# RADIO.net
KiCad netlist of a schematic drawn in EAGLE
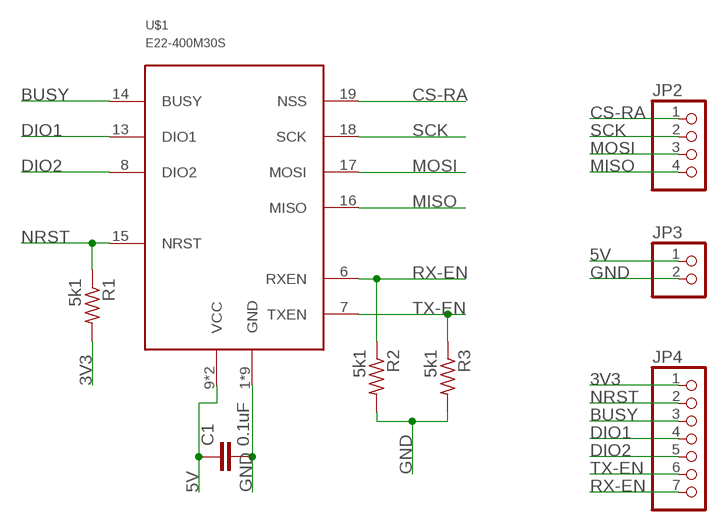
[diagram p0: schematic, sheet 1]

(export (version "E")
  (design (tool "Eeschema 10.0.6"))
  (components
    (comp (ref "C1")
      (value "0.1uF")
      (footprint "eagle-import:C0603")
      (libsource (lib "eagle-import") (part "C-EUC0603"))
    )
    (comp (ref "JP2")
      (value "PINHD-1X4")
      (footprint "eagle-import:1X04")
      (libsource (lib "eagle-import") (part "PINHD-1X4"))
    )
    (comp (ref "JP3")
      (value "PINHD-1X2")
      (footprint "eagle-import:1X02")
      (libsource (lib "eagle-import") (part "PINHD-1X2"))
    )
    (comp (ref "JP4")
      (value "PINHD-1X7")
      (footprint "eagle-import:1X07")
      (libsource (lib "eagle-import") (part "PINHD-1X7"))
    )
    (comp (ref "R1")
      (value "5k1")
      (footprint "eagle-import:R0603")
      (libsource (lib "eagle-import") (part "R-US_R0603"))
    )
    (comp (ref "R2")
      (value "5k1")
      (footprint "eagle-import:R0603")
      (libsource (lib "eagle-import") (part "R-US_R0603"))
    )
    (comp (ref "R3")
      (value "5k1")
      (footprint "eagle-import:R0603")
      (libsource (lib "eagle-import") (part "R-US_R0603"))
    )
    (comp (ref "U$1")
      (value "E22-400M30S")
      (footprint "eagle-import:E22-400M30S")
      (libsource (lib "eagle-import") (part "E22-400M30S"))
    )
  )
  (nets
    (net (code "1") (name "/3V3") (class "Default")
      (node (ref "JP4") (pin "1") (pinfunction "1_1") (pintype "passive"))
      (node (ref "R1") (pin "2") (pinfunction "2_2") (pintype "passive"))
    )
    (net (code "2") (name "/5V") (class "Default")
      (node (ref "C1") (pin "1") (pinfunction "1_1") (pintype "passive"))
      (node (ref "JP3") (pin "1") (pinfunction "1_1") (pintype "passive"))
      (node (ref "U$1") (pin "10") (pinfunction "VCC_10") (pintype "power_in"))
      (node (ref "U$1") (pin "9") (pinfunction "VCC_9") (pintype "power_in"))
    )
    (net (code "3") (name "/BUSY") (class "Default")
      (node (ref "JP4") (pin "3") (pinfunction "3_3") (pintype "passive"))
      (node (ref "U$1") (pin "14") (pinfunction "BUSY_14") (pintype "output"))
    )
    (net (code "4") (name "/CS-RA") (class "Default")
      (node (ref "JP2") (pin "1") (pinfunction "1_1") (pintype "passive"))
      (node (ref "U$1") (pin "19") (pinfunction "NSS_19") (pintype "input"))
    )
    (net (code "5") (name "/DIO1") (class "Default")
      (node (ref "JP4") (pin "4") (pinfunction "4_4") (pintype "passive"))
      (node (ref "U$1") (pin "13") (pinfunction "DIO1_13") (pintype "bidirectional"))
    )
    (net (code "6") (name "/DIO2") (class "Default")
      (node (ref "JP4") (pin "5") (pinfunction "5_5") (pintype "passive"))
      (node (ref "U$1") (pin "8") (pinfunction "DIO2_8") (pintype "bidirectional"))
    )
    (net (code "7") (name "/GND") (class "Default")
      (node (ref "C1") (pin "2") (pinfunction "2_2") (pintype "passive"))
      (node (ref "JP3") (pin "2") (pinfunction "2_2") (pintype "passive"))
      (node (ref "R2") (pin "2") (pinfunction "2_2") (pintype "passive"))
      (node (ref "R3") (pin "2") (pinfunction "2_2") (pintype "passive"))
      (node (ref "U$1") (pin "1") (pinfunction "GND_1") (pintype "power_in"))
      (node (ref "U$1") (pin "11") (pinfunction "GND_11") (pintype "power_in"))
      (node (ref "U$1") (pin "12") (pinfunction "GND_12") (pintype "power_in"))
      (node (ref "U$1") (pin "2") (pinfunction "GND_2") (pintype "power_in"))
      (node (ref "U$1") (pin "20") (pinfunction "GND_20") (pintype "power_in"))
      (node (ref "U$1") (pin "22") (pinfunction "GND_22") (pintype "power_in"))
      (node (ref "U$1") (pin "3") (pinfunction "GND_3") (pintype "power_in"))
      (node (ref "U$1") (pin "4") (pinfunction "GND_4") (pintype "power_in"))
      (node (ref "U$1") (pin "5") (pinfunction "GND_5") (pintype "power_in"))
    )
    (net (code "8") (name "/MISO") (class "Default")
      (node (ref "JP2") (pin "4") (pinfunction "4_4") (pintype "passive"))
      (node (ref "U$1") (pin "16") (pinfunction "MISO_16") (pintype "output"))
    )
    (net (code "9") (name "/MOSI") (class "Default")
      (node (ref "JP2") (pin "3") (pinfunction "3_3") (pintype "passive"))
      (node (ref "U$1") (pin "17") (pinfunction "MOSI_17") (pintype "input"))
    )
    (net (code "10") (name "/NRST") (class "Default")
      (node (ref "JP4") (pin "2") (pinfunction "2_2") (pintype "passive"))
      (node (ref "R1") (pin "1") (pinfunction "1_1") (pintype "passive"))
      (node (ref "U$1") (pin "15") (pinfunction "NRST_15") (pintype "input"))
    )
    (net (code "11") (name "/RX-EN") (class "Default")
      (node (ref "JP4") (pin "7") (pinfunction "7_7") (pintype "passive"))
      (node (ref "R2") (pin "1") (pinfunction "1_1") (pintype "passive"))
      (node (ref "U$1") (pin "6") (pinfunction "RXEN_6") (pintype "input"))
    )
    (net (code "12") (name "/SCK") (class "Default")
      (node (ref "JP2") (pin "2") (pinfunction "2_2") (pintype "passive"))
      (node (ref "U$1") (pin "18") (pinfunction "SCK_18") (pintype "input"))
    )
    (net (code "13") (name "/TX-EN") (class "Default")
      (node (ref "JP4") (pin "6") (pinfunction "6_6") (pintype "passive"))
      (node (ref "R3") (pin "1") (pinfunction "1_1") (pintype "passive"))
      (node (ref "U$1") (pin "7") (pinfunction "TXEN_7") (pintype "input"))
    )
  )
)
